# Naxida_Eyes_Down.net
KiCad netlist of a schematic drawn in Altium Designer
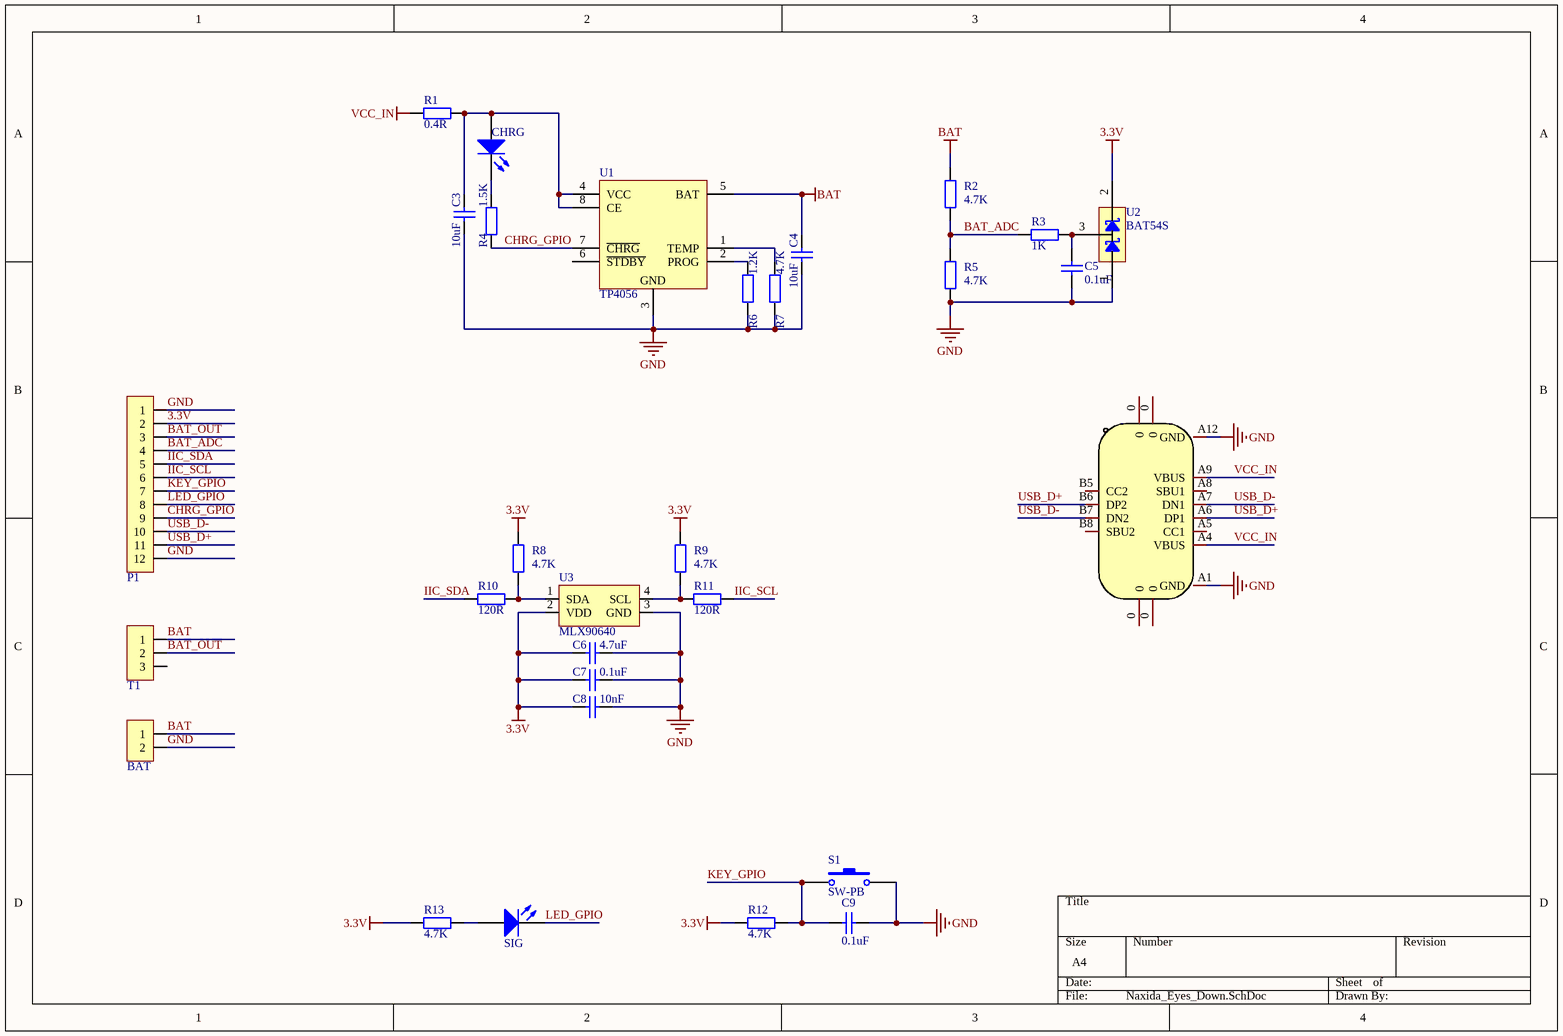
[diagram p0: Naxida_Eyes_Down.SchDoc]

(export (version "E")
  (design (tool "Eeschema 10.0.6"))
  (components
    (comp (ref "BAT")
      (value "Header 2*1")
      (footprint "COM_T_2.0_2P")
      (description "接插件")
      (fields (field (name "PUBLISHER") "Altium Limited"))
      (libsource (lib "Connect") (part "Header 2*1"))
    )
    (comp (ref "C3")
      (value "10uF")
      (footprint "LC-1206_C")
      (description "无极性电容")
      (fields (field (name "PUBLISHER") "Altium Limited"))
      (libsource (lib "Fszhang") (part "Cap"))
    )
    (comp (ref "C4")
      (value "10uF")
      (footprint "LC-1206_C")
      (description "无极性电容")
      (fields (field (name "PUBLISHER") "Altium Limited"))
      (libsource (lib "Fszhang") (part "Cap"))
    )
    (comp (ref "C5")
      (value "0.1uF")
      (footprint "LC-0603_C")
      (description "无极性电容")
      (fields (field (name "PUBLISHER") "Altium Limited"))
      (libsource (lib "Fszhang") (part "Cap"))
    )
    (comp (ref "C6")
      (value "4.7uF")
      (footprint "LC-0603_C")
      (description "无极性电容")
      (fields (field (name "PUBLISHER") "Altium Limited"))
      (libsource (lib "Fszhang") (part "Cap"))
    )
    (comp (ref "C7")
      (value "0.1uF")
      (footprint "LC-0603_C")
      (description "无极性电容")
      (fields (field (name "PUBLISHER") "Altium Limited"))
      (libsource (lib "Fszhang") (part "Cap"))
    )
    (comp (ref "C8")
      (value "10nF")
      (footprint "LC-0603_C")
      (description "无极性电容")
      (fields (field (name "PUBLISHER") "Altium Limited"))
      (libsource (lib "Fszhang") (part "Cap"))
    )
    (comp (ref "C9")
      (value "0.1uF")
      (footprint "LC-0603_C")
      (description "无极性电容")
      (fields (field (name "Comment") "Cap") (field (name "PUBLISHER") "Altium Limited"))
      (libsource (lib "Fszhang") (part "Cap"))
    )
    (comp (ref "CHRG")
      (value "LED0")
      (footprint "LC-0603_LED_S1")
      (description "发光二极管")
      (fields (field (name "PUBLISHER") "Altium Limited"))
      (libsource (lib "Fszhang") (part "LED0"))
    )
    (comp (ref "P1")
      (value "Header 12*1")
      (footprint "HDR12X1_A-1.27mm")
      (description "接插件")
      (fields (field (name "PUBLISHER") "Altium Limited"))
      (libsource (lib "Connect") (part "Header 12*1"))
    )
    (comp (ref "R1")
      (value "0.4R")
      (footprint "LC-1206_R")
      (description "贴片电阻")
      (fields (field (name "PUBLISHER") "Altium Limited"))
      (libsource (lib "") (part "=VALUE_2"))
    )
    (comp (ref "R2")
      (value "4.7K")
      (footprint "LC-0603_R")
      (description "贴片电阻")
      (fields (field (name "PUBLISHER") "Altium Limited"))
      (libsource (lib "Fszhang") (part "=VALUE"))
    )
    (comp (ref "R3")
      (value "1K")
      (footprint "LC-0603_R")
      (description "贴片电阻")
      (fields (field (name "PUBLISHER") "Altium Limited"))
      (libsource (lib "Fszhang") (part "Res1"))
    )
    (comp (ref "R4")
      (value "1.5K")
      (footprint "LC-0603_R")
      (description "贴片电阻")
      (fields (field (name "PUBLISHER") "Altium Limited"))
      (libsource (lib "Fszhang") (part "=VALUE"))
    )
    (comp (ref "R5")
      (value "4.7K")
      (footprint "LC-0603_R")
      (description "贴片电阻")
      (fields (field (name "PUBLISHER") "Altium Limited"))
      (libsource (lib "Fszhang") (part "=VALUE"))
    )
    (comp (ref "R6")
      (value "1.2K")
      (footprint "LC-0603_R")
      (description "贴片电阻")
      (fields (field (name "PUBLISHER") "Altium Limited"))
      (libsource (lib "Fszhang") (part "=VALUE"))
    )
    (comp (ref "R7")
      (value "4.7K")
      (footprint "LC-0603_R")
      (description "贴片电阻")
      (fields (field (name "PUBLISHER") "Altium Limited"))
      (libsource (lib "Fszhang") (part "=VALUE"))
    )
    (comp (ref "R8")
      (value "4.7K")
      (footprint "LC-0603_R")
      (description "贴片电阻")
      (fields (field (name "PUBLISHER") "Altium Limited"))
      (libsource (lib "Fszhang") (part "=VALUE"))
    )
    (comp (ref "R9")
      (value "4.7K")
      (footprint "LC-0603_R")
      (description "贴片电阻")
      (fields (field (name "PUBLISHER") "Altium Limited"))
      (libsource (lib "Fszhang") (part "=VALUE"))
    )
    (comp (ref "R10")
      (value "120R")
      (footprint "LC-0603_R")
      (description "贴片电阻")
      (fields (field (name "PUBLISHER") "Altium Limited"))
      (libsource (lib "") (part "=VALUE_1"))
    )
    (comp (ref "R11")
      (value "120R")
      (footprint "LC-0603_R")
      (description "贴片电阻")
      (fields (field (name "PUBLISHER") "Altium Limited"))
      (libsource (lib "") (part "=VALUE_1"))
    )
    (comp (ref "R12")
      (value "4.7K")
      (footprint "LC-0603_R")
      (description "贴片电阻")
      (fields (field (name "Comment") "Res1") (field (name "PUBLISHER") "Altium Limited"))
      (libsource (lib "Fszhang") (part "Res1"))
    )
    (comp (ref "R13")
      (value "4.7K")
      (footprint "LC-0603_R")
      (description "贴片电阻")
      (fields (field (name "Comment") "Res1") (field (name "PUBLISHER") "Altium Limited"))
      (libsource (lib "Fszhang") (part "Res1"))
    )
    (comp (ref "S1")
      (value "SW-PB")
      (footprint "KEY_3*6*3.5")
      (description "微动开关")
      (fields (field (name "PUBLISHER") "Altium Limited"))
      (libsource (lib "Fszhang") (part "SW-PB"))
    )
    (comp (ref "SIG")
      (value "LED0")
      (footprint "LC-0603_LED_S1")
      (description "发光二极管")
      (fields (field (name "PUBLISHER") "Altium Limited"))
      (libsource (lib "Fszhang") (part "LED0"))
    )
    (comp (ref "T1")
      (value "Header 3*1")
      (footprint "KEY_3*7")
      (description "接插件")
      (fields (field (name "PUBLISHER") "Altium Limited"))
      (libsource (lib "Connect") (part "Header 3*1"))
    )
    (comp (ref "U1")
      (value "TP4056")
      (footprint "ESOP_4056")
      (description "锂电池充电管理")
      (libsource (lib "Fszhang") (part "TP4056"))
    )
    (comp (ref "U2")
      (value "BAT54S")
      (footprint "SOT-23")
      (description "肖特基二极管")
      (libsource (lib "Fszhang") (part "BAT54S"))
    )
    (comp (ref "U3")
      (value "MLX90640")
      (footprint "MLX90640")
      (libsource (lib "Zfy_Library") (part "MLX90640"))
    )
    (comp (ref "USBC1")
      (value "TYPE-C")
      (footprint "TYPE-C-16P")
      (fields (field (name "MANUFACTURER") "精拓金") (field (name "MANUFACTURER PART") "918-418K2023S40001"))
      (libsource (lib "Zfy_Library") (part "TYPE-C"))
    )
  )
  (nets
    (net (code "1") (name "/BAT_ADC") (class "Default")
      (node (ref "P1") (pin "4") (pinfunction "4_4") (pintype "passive"))
      (node (ref "R2") (pin "2") (pinfunction "2_2") (pintype "passive"))
      (node (ref "R3") (pin "1") (pinfunction "1_1") (pintype "passive"))
      (node (ref "R5") (pin "1") (pinfunction "1_1") (pintype "passive"))
    )
    (net (code "2") (name "/BAT_OUT") (class "Default")
      (node (ref "P1") (pin "3") (pinfunction "3_3") (pintype "passive"))
      (node (ref "T1") (pin "2") (pinfunction "2_2") (pintype "passive"))
    )
    (net (code "3") (name "/CHRG_GPIO") (class "Default")
      (node (ref "P1") (pin "9") (pinfunction "9_9") (pintype "passive"))
      (node (ref "R4") (pin "2") (pinfunction "2_2") (pintype "passive"))
      (node (ref "U1") (pin "7") (pinfunction "~{CHRG}_7") (pintype "passive"))
    )
    (net (code "4") (name "/IIC_SCL") (class "Default")
      (node (ref "P1") (pin "6") (pinfunction "6_6") (pintype "passive"))
      (node (ref "R11") (pin "2") (pinfunction "2_2") (pintype "passive"))
    )
    (net (code "5") (name "/IIC_SDA") (class "Default")
      (node (ref "P1") (pin "5") (pinfunction "5_5") (pintype "passive"))
      (node (ref "R10") (pin "1") (pinfunction "1_1") (pintype "passive"))
    )
    (net (code "6") (name "/KEY_GPIO") (class "Default")
      (node (ref "C9") (pin "1") (pinfunction "1_1") (pintype "passive"))
      (node (ref "P1") (pin "7") (pinfunction "7_7") (pintype "passive"))
      (node (ref "R12") (pin "2") (pinfunction "2_2") (pintype "passive"))
      (node (ref "S1") (pin "1") (pinfunction "1_1") (pintype "passive"))
    )
    (net (code "7") (name "/LED_GPIO") (class "Default")
      (node (ref "P1") (pin "8") (pinfunction "8_8") (pintype "passive"))
      (node (ref "SIG") (pin "2") (pinfunction "K_2") (pintype "passive"))
    )
    (net (code "8") (name "/USB_D+") (class "Default")
      (node (ref "P1") (pin "11") (pinfunction "11_11") (pintype "passive"))
      (node (ref "USBC1") (pin "A6") (pinfunction "DP1_A6") (pintype "passive"))
      (node (ref "USBC1") (pin "B6") (pinfunction "DP2_B6") (pintype "passive"))
    )
    (net (code "9") (name "/USB_D-") (class "Default")
      (node (ref "P1") (pin "10") (pinfunction "10_10") (pintype "passive"))
      (node (ref "USBC1") (pin "A7") (pinfunction "DN1_A7") (pintype "passive"))
      (node (ref "USBC1") (pin "B7") (pinfunction "DN2_B7") (pintype "passive"))
    )
    (net (code "10") (name "3.3V") (class "Default")
      (node (ref "C6") (pin "2") (pinfunction "2_2") (pintype "passive"))
      (node (ref "C7") (pin "2") (pinfunction "2_2") (pintype "passive"))
      (node (ref "C8") (pin "2") (pinfunction "2_2") (pintype "passive"))
      (node (ref "P1") (pin "2") (pinfunction "2_2") (pintype "passive"))
      (node (ref "R12") (pin "1") (pinfunction "1_1") (pintype "passive"))
      (node (ref "R13") (pin "1") (pinfunction "1_1") (pintype "passive"))
      (node (ref "R8") (pin "1") (pinfunction "1_1") (pintype "passive"))
      (node (ref "R9") (pin "1") (pinfunction "1_1") (pintype "passive"))
      (node (ref "U2") (pin "2") (pinfunction "2_2") (pintype "passive"))
      (node (ref "U3") (pin "2") (pinfunction "VDD_2") (pintype "passive"))
    )
    (net (code "11") (name "BAT") (class "Default")
      (node (ref "BAT") (pin "1") (pinfunction "1_1") (pintype "passive"))
      (node (ref "C4") (pin "2") (pinfunction "2_2") (pintype "passive"))
      (node (ref "R2") (pin "1") (pinfunction "1_1") (pintype "passive"))
      (node (ref "T1") (pin "1") (pinfunction "1_1") (pintype "passive"))
      (node (ref "U1") (pin "5") (pinfunction "BAT_5") (pintype "passive"))
    )
    (net (code "12") (name "GND") (class "Default")
      (node (ref "BAT") (pin "2") (pinfunction "2_2") (pintype "passive"))
      (node (ref "C3") (pin "1") (pinfunction "1_1") (pintype "passive"))
      (node (ref "C4") (pin "1") (pinfunction "1_1") (pintype "passive"))
      (node (ref "C5") (pin "1") (pinfunction "1_1") (pintype "passive"))
      (node (ref "C6") (pin "1") (pinfunction "1_1") (pintype "passive"))
      (node (ref "C7") (pin "1") (pinfunction "1_1") (pintype "passive"))
      (node (ref "C8") (pin "1") (pinfunction "1_1") (pintype "passive"))
      (node (ref "C9") (pin "2") (pinfunction "2_2") (pintype "passive"))
      (node (ref "P1") (pin "1") (pinfunction "1_1") (pintype "passive"))
      (node (ref "P1") (pin "12") (pinfunction "12_12") (pintype "passive"))
      (node (ref "R5") (pin "2") (pinfunction "2_2") (pintype "passive"))
      (node (ref "R6") (pin "2") (pinfunction "2_2") (pintype "passive"))
      (node (ref "R7") (pin "2") (pinfunction "2_2") (pintype "passive"))
      (node (ref "S1") (pin "2") (pinfunction "2_2") (pintype "passive"))
      (node (ref "U1") (pin "3") (pinfunction "GND_3") (pintype "passive"))
      (node (ref "U2") (pin "1") (pinfunction "1_1") (pintype "passive"))
      (node (ref "U3") (pin "3") (pinfunction "GND_3") (pintype "passive"))
      (node (ref "USBC1") (pin "A1") (pinfunction "GND_A1") (pintype "passive"))
      (node (ref "USBC1") (pin "A12") (pinfunction "GND_A12") (pintype "passive"))
    )
    (net (code "13") (name "Net-(C5-Pad2)") (class "Default")
      (node (ref "C5") (pin "2") (pinfunction "2_2") (pintype "passive"))
      (node (ref "R3") (pin "2") (pinfunction "2_2") (pintype "passive"))
      (node (ref "U2") (pin "3") (pinfunction "3_3") (pintype "passive"))
    )
    (net (code "14") (name "Net-(CHRG-A)") (class "Default")
      (node (ref "C3") (pin "2") (pinfunction "2_2") (pintype "passive"))
      (node (ref "CHRG") (pin "1") (pinfunction "A_1") (pintype "passive"))
      (node (ref "R1") (pin "1") (pinfunction "1_1") (pintype "passive"))
      (node (ref "U1") (pin "4") (pinfunction "VCC_4") (pintype "passive"))
      (node (ref "U1") (pin "8") (pinfunction "CE_8") (pintype "passive"))
    )
    (net (code "15") (name "Net-(CHRG-K)") (class "Default")
      (node (ref "CHRG") (pin "2") (pinfunction "K_2") (pintype "passive"))
      (node (ref "R4") (pin "1") (pinfunction "1_1") (pintype "passive"))
    )
    (net (code "16") (name "Net-(SIG-A)") (class "Default")
      (node (ref "R13") (pin "2") (pinfunction "2_2") (pintype "passive"))
      (node (ref "SIG") (pin "1") (pinfunction "A_1") (pintype "passive"))
    )
    (net (code "17") (name "Net-(U1-PROG)") (class "Default")
      (node (ref "R6") (pin "1") (pinfunction "1_1") (pintype "passive"))
      (node (ref "U1") (pin "2") (pinfunction "PROG_2") (pintype "passive"))
    )
    (net (code "18") (name "Net-(U1-TEMP)") (class "Default")
      (node (ref "R7") (pin "1") (pinfunction "1_1") (pintype "passive"))
      (node (ref "U1") (pin "1") (pinfunction "TEMP_1") (pintype "passive"))
    )
    (net (code "19") (name "Net-(U3-SCL)") (class "Default")
      (node (ref "R11") (pin "1") (pinfunction "1_1") (pintype "passive"))
      (node (ref "R9") (pin "2") (pinfunction "2_2") (pintype "passive"))
      (node (ref "U3") (pin "4") (pinfunction "SCL_4") (pintype "passive"))
    )
    (net (code "20") (name "Net-(U3-SDA)") (class "Default")
      (node (ref "R10") (pin "2") (pinfunction "2_2") (pintype "passive"))
      (node (ref "R8") (pin "2") (pinfunction "2_2") (pintype "passive"))
      (node (ref "U3") (pin "1") (pinfunction "SDA_1") (pintype "passive"))
    )
    (net (code "21") (name "VCC_IN") (class "Default")
      (node (ref "R1") (pin "2") (pinfunction "2_2") (pintype "passive"))
      (node (ref "USBC1") (pin "A4") (pinfunction "VBUS_A4") (pintype "passive"))
      (node (ref "USBC1") (pin "A9") (pinfunction "VBUS_A9") (pintype "passive"))
    )
    (net (code "22") (name "unconnected-(T1-Pad3)") (class "Default")
      (node (ref "T1") (pin "3") (pinfunction "3_3") (pintype "passive"))
    )
    (net (code "23") (name "unconnected-(U1-~{STDBY}-Pad6)") (class "Default")
      (node (ref "U1") (pin "6") (pinfunction "~{STDBY}_6") (pintype "passive"))
    )
    (net (code "24") (name "unconnected-(USBC1-CC1-PadA5)") (class "Default")
      (node (ref "USBC1") (pin "A5") (pinfunction "CC1_A5") (pintype "passive"))
    )
    (net (code "25") (name "unconnected-(USBC1-CC2-PadB5)") (class "Default")
      (node (ref "USBC1") (pin "B5") (pinfunction "CC2_B5") (pintype "passive"))
    )
    (net (code "26") (name "unconnected-(USBC1-Pad0)") (class "Default")
      (node (ref "USBC1") (pin "0") (pinfunction "0_0") (pintype "passive"))
    )
    (net (code "27") (name "unconnected-(USBC1-Pad0)_1") (class "Default")
      (node (ref "USBC1") (pin "0") (pinfunction "0_0") (pintype "passive"))
    )
    (net (code "28") (name "unconnected-(USBC1-Pad0)_2") (class "Default")
      (node (ref "USBC1") (pin "0") (pinfunction "0_0") (pintype "passive"))
    )
    (net (code "29") (name "unconnected-(USBC1-Pad0)_3") (class "Default")
      (node (ref "USBC1") (pin "0") (pinfunction "0_0") (pintype "passive"))
    )
    (net (code "30") (name "unconnected-(USBC1-SBU1-PadA8)") (class "Default")
      (node (ref "USBC1") (pin "A8") (pinfunction "SBU1_A8") (pintype "passive"))
    )
    (net (code "31") (name "unconnected-(USBC1-SBU2-PadB8)") (class "Default")
      (node (ref "USBC1") (pin "B8") (pinfunction "SBU2_B8") (pintype "passive"))
    )
  )
)
